# DASH_BOARD_V_2_0.net
KiCad netlist of a schematic drawn in EAGLE
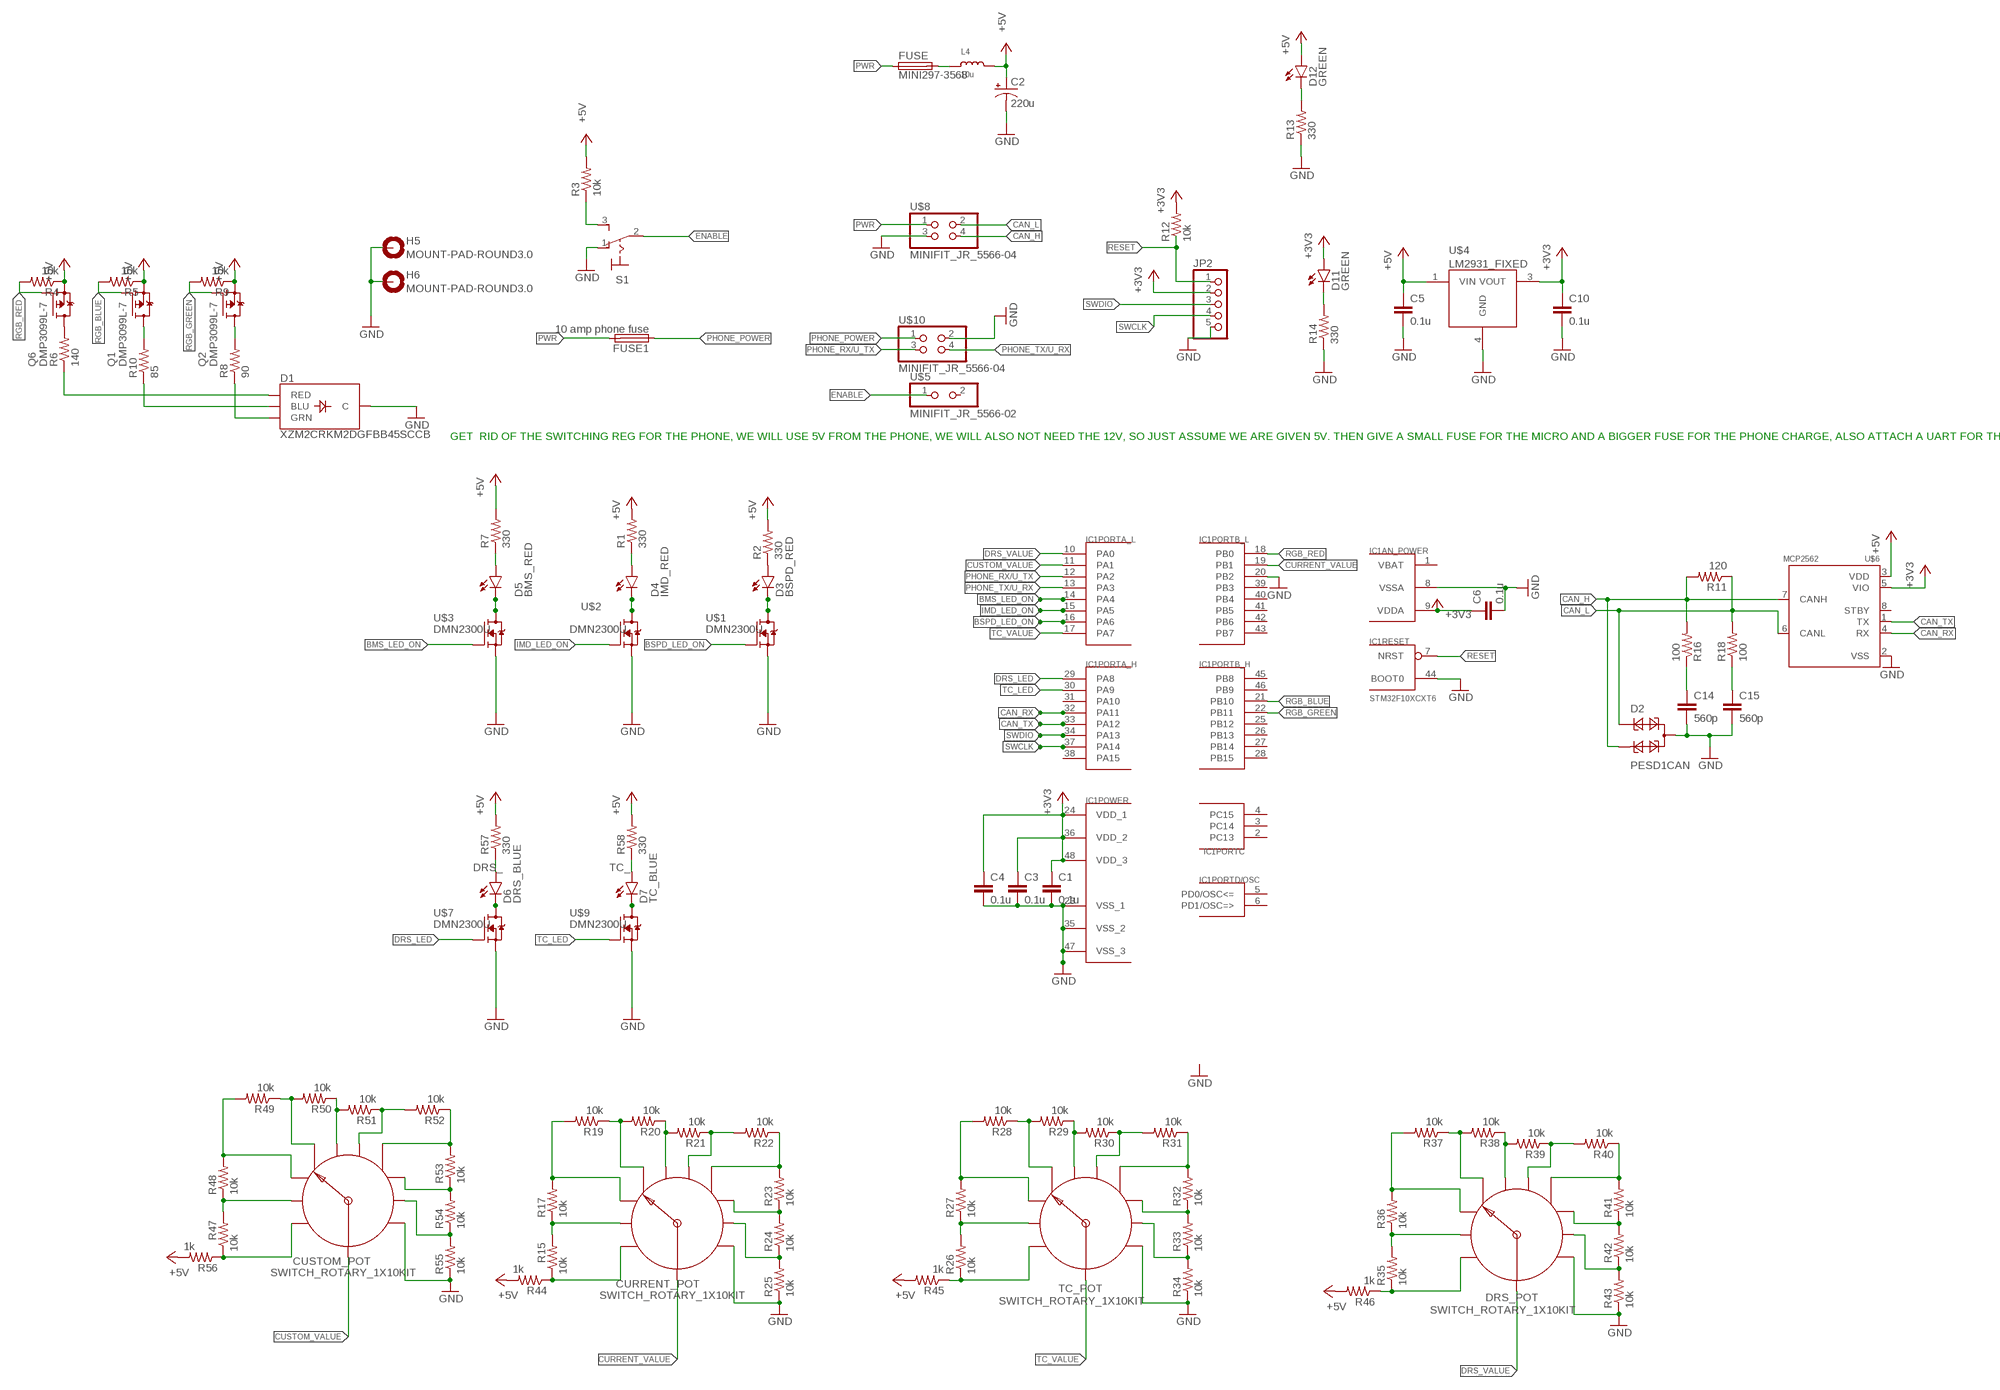
[diagram p0: schematic, sheet 1]

(export (version "E")
  (design (tool "Eeschema 10.0.6"))
  (components
    (comp (ref "C1")
      (value "0.1u")
      (footprint "eagle-import:C0805K")
      (libsource (lib "eagle-import") (part "C-EUC0805K"))
    )
    (comp (ref "C2")
      (value "220u")
      (footprint "eagle-import:E2,5-7")
      (libsource (lib "eagle-import") (part "CPOL-USE2.5-7"))
    )
    (comp (ref "C3")
      (value "0.1u")
      (footprint "eagle-import:C0805K")
      (libsource (lib "eagle-import") (part "C-EUC0805K"))
    )
    (comp (ref "C4")
      (value "0.1u")
      (footprint "eagle-import:C0805K")
      (libsource (lib "eagle-import") (part "C-EUC0805K"))
    )
    (comp (ref "C5")
      (value "0.1u")
      (footprint "eagle-import:C0805K")
      (libsource (lib "eagle-import") (part "C-EUC0805K"))
    )
    (comp (ref "C6")
      (value "0.1u")
      (footprint "eagle-import:C0805K")
      (libsource (lib "eagle-import") (part "C-EUC0805K"))
    )
    (comp (ref "C10")
      (value "0.1u")
      (footprint "eagle-import:C0805K")
      (libsource (lib "eagle-import") (part "C-EUC0805K"))
    )
    (comp (ref "C14")
      (value "560p")
      (footprint "eagle-import:C0805K")
      (libsource (lib "eagle-import") (part "C-EUC0805K"))
    )
    (comp (ref "C15")
      (value "560p")
      (footprint "eagle-import:C0805K")
      (libsource (lib "eagle-import") (part "C-EUC0805K"))
    )
    (comp (ref "CURRENT_POT")
      (value "SWITCH_ROTARY_1X10KIT")
      (footprint "eagle-import:ROTARY_SWITCH_1X10_KIT")
      (libsource (lib "eagle-import") (part "SWITCH_ROTARY_1X10KIT"))
    )
    (comp (ref "CUSTOM_POT")
      (value "SWITCH_ROTARY_1X10KIT")
      (footprint "eagle-import:ROTARY_SWITCH_1X10_KIT")
      (libsource (lib "eagle-import") (part "SWITCH_ROTARY_1X10KIT"))
    )
    (comp (ref "D1")
      (value "XZM2CRKM2DGFBB45SCCB")
      (footprint "eagle-import:PLCC4SMDLED")
      (libsource (lib "eagle-import") (part "SUNLEDSMD1"))
    )
    (comp (ref "D2")
      (value "PESD1CAN")
      (footprint "eagle-import:SOT23")
      (libsource (lib "eagle-import") (part "PESD1CAN"))
    )
    (comp (ref "D3")
      (value "BSPD_RED")
      (footprint "eagle-import:LED-0603")
      (libsource (lib "eagle-import") (part "LED-GREEN0603"))
    )
    (comp (ref "D4")
      (value "IMD_RED")
      (footprint "eagle-import:LED-0603")
      (libsource (lib "eagle-import") (part "LED-GREEN0603"))
    )
    (comp (ref "D5")
      (value "BMS_RED")
      (footprint "eagle-import:LED-0603")
      (libsource (lib "eagle-import") (part "LED-GREEN0603"))
    )
    (comp (ref "D6")
      (value "DRS_BLUE")
      (footprint "eagle-import:LED-0603")
      (libsource (lib "eagle-import") (part "LED-GREEN0603"))
    )
    (comp (ref "D7")
      (value "TC_BLUE")
      (footprint "eagle-import:LED-0603")
      (libsource (lib "eagle-import") (part "LED-GREEN0603"))
    )
    (comp (ref "D11")
      (value "GREEN")
      (footprint "eagle-import:LED-0603")
      (libsource (lib "eagle-import") (part "LED-GREEN0603"))
    )
    (comp (ref "D12")
      (value "GREEN")
      (footprint "eagle-import:LED-0603")
      (libsource (lib "eagle-import") (part "LED-GREEN0603"))
    )
    (comp (ref "DRS_POT")
      (value "SWITCH_ROTARY_1X10KIT")
      (footprint "eagle-import:ROTARY_SWITCH_1X10_KIT")
      (libsource (lib "eagle-import") (part "SWITCH_ROTARY_1X10KIT"))
    )
    (comp (ref "FUSE")
      (value "MINI297-3568")
      (footprint "eagle-import:3568")
      (libsource (lib "eagle-import") (part "MINI297-3568"))
    )
    (comp (ref "FUSE1")
      (value "10 amp phone fuse")
      (footprint "eagle-import:3568")
      (libsource (lib "eagle-import") (part "MINI297-3568"))
    )
    (comp (ref "H5")
      (value "MOUNT-PAD-ROUND3.0")
      (footprint "eagle-import:3,0-PAD")
      (libsource (lib "eagle-import") (part "MOUNT-PAD-ROUND3.0"))
    )
    (comp (ref "H6")
      (value "MOUNT-PAD-ROUND3.0")
      (footprint "eagle-import:3,0-PAD")
      (libsource (lib "eagle-import") (part "MOUNT-PAD-ROUND3.0"))
    )
    (comp (ref "IC1")
      (value "STM32F10XCXT6")
      (footprint "eagle-import:TQFP48")
      (libsource (lib "eagle-import") (part "STM32F10XCXT6"))
    )
    (comp (ref "JP2")
      (value "PINHD-1X5")
      (footprint "eagle-import:1X05")
      (libsource (lib "eagle-import") (part "PINHD-1X5"))
    )
    (comp (ref "L4")
      (value "10u")
      (footprint "eagle-import:INDUCTOR_5X5MM_NR5040_NOTHERMALS")
      (libsource (lib "eagle-import") (part "INDUCTORNR5040"))
    )
    (comp (ref "Q1")
      (value "DMP3099L-7")
      (footprint "eagle-import:SOT23")
      (libsource (lib "eagle-import") (part "DMP3099L-7"))
    )
    (comp (ref "Q2")
      (value "DMP3099L-7")
      (footprint "eagle-import:SOT23")
      (libsource (lib "eagle-import") (part "DMP3099L-7"))
    )
    (comp (ref "Q6")
      (value "DMP3099L-7")
      (footprint "eagle-import:SOT23")
      (libsource (lib "eagle-import") (part "DMP3099L-7"))
    )
    (comp (ref "R1")
      (value "330")
      (footprint "eagle-import:R0805")
      (libsource (lib "eagle-import") (part "resistor_348_R-US_R0805"))
    )
    (comp (ref "R2")
      (value "330")
      (footprint "eagle-import:R0805")
      (libsource (lib "eagle-import") (part "resistor_348_R-US_R0805"))
    )
    (comp (ref "R3")
      (value "10k")
      (footprint "eagle-import:R0805")
      (libsource (lib "eagle-import") (part "resistor_348_R-US_R0805"))
    )
    (comp (ref "R4")
      (value "10k")
      (footprint "eagle-import:R0805")
      (libsource (lib "eagle-import") (part "resistor_348_R-US_R0805"))
    )
    (comp (ref "R5")
      (value "10k")
      (footprint "eagle-import:R0805")
      (libsource (lib "eagle-import") (part "resistor_348_R-US_R0805"))
    )
    (comp (ref "R6")
      (value "140")
      (footprint "eagle-import:R0805")
      (libsource (lib "eagle-import") (part "resistor_348_R-US_R0805"))
    )
    (comp (ref "R7")
      (value "330")
      (footprint "eagle-import:R0805")
      (libsource (lib "eagle-import") (part "resistor_348_R-US_R0805"))
    )
    (comp (ref "R8")
      (value "90")
      (footprint "eagle-import:R0805")
      (libsource (lib "eagle-import") (part "resistor_348_R-US_R0805"))
    )
    (comp (ref "R9")
      (value "10k")
      (footprint "eagle-import:R0805")
      (libsource (lib "eagle-import") (part "resistor_348_R-US_R0805"))
    )
    (comp (ref "R10")
      (value "85")
      (footprint "eagle-import:R0805")
      (libsource (lib "eagle-import") (part "resistor_348_R-US_R0805"))
    )
    (comp (ref "R11")
      (value "120")
      (footprint "eagle-import:R0805")
      (libsource (lib "eagle-import") (part "R-US_R0805"))
    )
    (comp (ref "R12")
      (value "10k")
      (footprint "eagle-import:R0805")
      (libsource (lib "eagle-import") (part "resistor_348_R-US_R0805"))
    )
    (comp (ref "R13")
      (value "330")
      (footprint "eagle-import:R0603")
      (libsource (lib "eagle-import") (part "rcl_334_R-US_R0603"))
    )
    (comp (ref "R14")
      (value "330")
      (footprint "eagle-import:R0603")
      (libsource (lib "eagle-import") (part "rcl_334_R-US_R0603"))
    )
    (comp (ref "R15")
      (value "10k")
      (footprint "eagle-import:R0805")
      (libsource (lib "eagle-import") (part "resistor_348_R-US_R0805"))
    )
    (comp (ref "R16")
      (value "100")
      (footprint "eagle-import:R0805")
      (libsource (lib "eagle-import") (part "R-US_R0805"))
    )
    (comp (ref "R17")
      (value "10k")
      (footprint "eagle-import:R0805")
      (libsource (lib "eagle-import") (part "resistor_348_R-US_R0805"))
    )
    (comp (ref "R18")
      (value "100")
      (footprint "eagle-import:R0805")
      (libsource (lib "eagle-import") (part "R-US_R0805"))
    )
    (comp (ref "R19")
      (value "10k")
      (footprint "eagle-import:R0805")
      (libsource (lib "eagle-import") (part "resistor_348_R-US_R0805"))
    )
    (comp (ref "R20")
      (value "10k")
      (footprint "eagle-import:R0805")
      (libsource (lib "eagle-import") (part "resistor_348_R-US_R0805"))
    )
    (comp (ref "R21")
      (value "10k")
      (footprint "eagle-import:R0805")
      (libsource (lib "eagle-import") (part "resistor_348_R-US_R0805"))
    )
    (comp (ref "R22")
      (value "10k")
      (footprint "eagle-import:R0805")
      (libsource (lib "eagle-import") (part "resistor_348_R-US_R0805"))
    )
    (comp (ref "R23")
      (value "10k")
      (footprint "eagle-import:R0805")
      (libsource (lib "eagle-import") (part "resistor_348_R-US_R0805"))
    )
    (comp (ref "R24")
      (value "10k")
      (footprint "eagle-import:R0805")
      (libsource (lib "eagle-import") (part "resistor_348_R-US_R0805"))
    )
    (comp (ref "R25")
      (value "10k")
      (footprint "eagle-import:R0805")
      (libsource (lib "eagle-import") (part "resistor_348_R-US_R0805"))
    )
    (comp (ref "R26")
      (value "10k")
      (footprint "eagle-import:R0805")
      (libsource (lib "eagle-import") (part "resistor_348_R-US_R0805"))
    )
    (comp (ref "R27")
      (value "10k")
      (footprint "eagle-import:R0805")
      (libsource (lib "eagle-import") (part "resistor_348_R-US_R0805"))
    )
    (comp (ref "R28")
      (value "10k")
      (footprint "eagle-import:R0805")
      (libsource (lib "eagle-import") (part "resistor_348_R-US_R0805"))
    )
    (comp (ref "R29")
      (value "10k")
      (footprint "eagle-import:R0805")
      (libsource (lib "eagle-import") (part "resistor_348_R-US_R0805"))
    )
    (comp (ref "R30")
      (value "10k")
      (footprint "eagle-import:R0805")
      (libsource (lib "eagle-import") (part "resistor_348_R-US_R0805"))
    )
    (comp (ref "R31")
      (value "10k")
      (footprint "eagle-import:R0805")
      (libsource (lib "eagle-import") (part "resistor_348_R-US_R0805"))
    )
    (comp (ref "R32")
      (value "10k")
      (footprint "eagle-import:R0805")
      (libsource (lib "eagle-import") (part "resistor_348_R-US_R0805"))
    )
    (comp (ref "R33")
      (value "10k")
      (footprint "eagle-import:R0805")
      (libsource (lib "eagle-import") (part "resistor_348_R-US_R0805"))
    )
    (comp (ref "R34")
      (value "10k")
      (footprint "eagle-import:R0805")
      (libsource (lib "eagle-import") (part "resistor_348_R-US_R0805"))
    )
    (comp (ref "R35")
      (value "10k")
      (footprint "eagle-import:R0805")
      (libsource (lib "eagle-import") (part "resistor_348_R-US_R0805"))
    )
    (comp (ref "R36")
      (value "10k")
      (footprint "eagle-import:R0805")
      (libsource (lib "eagle-import") (part "resistor_348_R-US_R0805"))
    )
    (comp (ref "R37")
      (value "10k")
      (footprint "eagle-import:R0805")
      (libsource (lib "eagle-import") (part "resistor_348_R-US_R0805"))
    )
    (comp (ref "R38")
      (value "10k")
      (footprint "eagle-import:R0805")
      (libsource (lib "eagle-import") (part "resistor_348_R-US_R0805"))
    )
    (comp (ref "R39")
      (value "10k")
      (footprint "eagle-import:R0805")
      (libsource (lib "eagle-import") (part "resistor_348_R-US_R0805"))
    )
    (comp (ref "R40")
      (value "10k")
      (footprint "eagle-import:R0805")
      (libsource (lib "eagle-import") (part "resistor_348_R-US_R0805"))
    )
    (comp (ref "R41")
      (value "10k")
      (footprint "eagle-import:R0805")
      (libsource (lib "eagle-import") (part "resistor_348_R-US_R0805"))
    )
    (comp (ref "R42")
      (value "10k")
      (footprint "eagle-import:R0805")
      (libsource (lib "eagle-import") (part "resistor_348_R-US_R0805"))
    )
    (comp (ref "R43")
      (value "10k")
      (footprint "eagle-import:R0805")
      (libsource (lib "eagle-import") (part "resistor_348_R-US_R0805"))
    )
    (comp (ref "R44")
      (value "1k")
      (footprint "eagle-import:R0805")
      (libsource (lib "eagle-import") (part "resistor_348_R-US_R0805"))
    )
    (comp (ref "R45")
      (value "1k")
      (footprint "eagle-import:R0805")
      (libsource (lib "eagle-import") (part "resistor_348_R-US_R0805"))
    )
    (comp (ref "R46")
      (value "1k")
      (footprint "eagle-import:R0805")
      (libsource (lib "eagle-import") (part "resistor_348_R-US_R0805"))
    )
    (comp (ref "R47")
      (value "10k")
      (footprint "eagle-import:R0805")
      (libsource (lib "eagle-import") (part "resistor_348_R-US_R0805"))
    )
    (comp (ref "R48")
      (value "10k")
      (footprint "eagle-import:R0805")
      (libsource (lib "eagle-import") (part "resistor_348_R-US_R0805"))
    )
    (comp (ref "R49")
      (value "10k")
      (footprint "eagle-import:R0805")
      (libsource (lib "eagle-import") (part "resistor_348_R-US_R0805"))
    )
    (comp (ref "R50")
      (value "10k")
      (footprint "eagle-import:R0805")
      (libsource (lib "eagle-import") (part "resistor_348_R-US_R0805"))
    )
    (comp (ref "R51")
      (value "10k")
      (footprint "eagle-import:R0805")
      (libsource (lib "eagle-import") (part "resistor_348_R-US_R0805"))
    )
    (comp (ref "R52")
      (value "10k")
      (footprint "eagle-import:R0805")
      (libsource (lib "eagle-import") (part "resistor_348_R-US_R0805"))
    )
    (comp (ref "R53")
      (value "10k")
      (footprint "eagle-import:R0805")
      (libsource (lib "eagle-import") (part "resistor_348_R-US_R0805"))
    )
    (comp (ref "R54")
      (value "10k")
      (footprint "eagle-import:R0805")
      (libsource (lib "eagle-import") (part "resistor_348_R-US_R0805"))
    )
    (comp (ref "R55")
      (value "10k")
      (footprint "eagle-import:R0805")
      (libsource (lib "eagle-import") (part "resistor_348_R-US_R0805"))
    )
    (comp (ref "R56")
      (value "1k")
      (footprint "eagle-import:R0805")
      (libsource (lib "eagle-import") (part "resistor_348_R-US_R0805"))
    )
    (comp (ref "R57")
      (value "330")
      (footprint "eagle-import:R0805")
      (libsource (lib "eagle-import") (part "resistor_348_R-US_R0805"))
    )
    (comp (ref "R58")
      (value "330")
      (footprint "eagle-import:R0805")
      (libsource (lib "eagle-import") (part "resistor_348_R-US_R0805"))
    )
    (comp (ref "S1")
      (value "320-916")
      (footprint "eagle-import:320-916")
      (libsource (lib "eagle-import") (part "320-916"))
    )
    (comp (ref "TC_POT")
      (value "SWITCH_ROTARY_1X10KIT")
      (footprint "eagle-import:ROTARY_SWITCH_1X10_KIT")
      (libsource (lib "eagle-import") (part "SWITCH_ROTARY_1X10KIT"))
    )
    (comp (ref "U$1")
      (value "DMN2300U")
      (footprint "eagle-import:SOT23")
      (libsource (lib "eagle-import") (part "DMN2300U"))
    )
    (comp (ref "U$2")
      (value "DMN2300U")
      (footprint "eagle-import:SOT23")
      (libsource (lib "eagle-import") (part "DMN2300U"))
    )
    (comp (ref "U$3")
      (value "DMN2300U")
      (footprint "eagle-import:SOT23")
      (libsource (lib "eagle-import") (part "DMN2300U"))
    )
    (comp (ref "U$4")
      (value "LM2931_FIXED")
      (footprint "eagle-import:DPAK")
      (libsource (lib "eagle-import") (part "LM2931_FIXED"))
    )
    (comp (ref "U$5")
      (value "MINIFIT_JR_5566-02")
      (footprint "eagle-import:MINIFIT_JR_5566-02")
      (libsource (lib "eagle-import") (part "MINIFIT_JR_5566-02"))
    )
    (comp (ref "U$6")
      (value "MCP2562")
      (footprint "eagle-import:SOIC8")
      (libsource (lib "eagle-import") (part "MCP2562"))
    )
    (comp (ref "U$7")
      (value "DMN2300U")
      (footprint "eagle-import:SOT23")
      (libsource (lib "eagle-import") (part "DMN2300U"))
    )
    (comp (ref "U$8")
      (value "MINIFIT_JR_5566-04")
      (footprint "eagle-import:MINIFIT_JR_5566-04")
      (libsource (lib "eagle-import") (part "MINIFIT_JR_5566-04"))
    )
    (comp (ref "U$9")
      (value "DMN2300U")
      (footprint "eagle-import:SOT23")
      (libsource (lib "eagle-import") (part "DMN2300U"))
    )
    (comp (ref "U$10")
      (value "MINIFIT_JR_5566-04")
      (footprint "eagle-import:MINIFIT_JR_5566-04")
      (libsource (lib "eagle-import") (part "MINIFIT_JR_5566-04"))
    )
  )
  (nets
    (net (code "1") (name "+3V3") (class "Default")
      (node (ref "C1") (pin "1") (pinfunction "1_1") (pintype "passive"))
      (node (ref "C10") (pin "1") (pinfunction "1_1") (pintype "passive"))
      (node (ref "C3") (pin "1") (pinfunction "1_1") (pintype "passive"))
      (node (ref "C4") (pin "1") (pinfunction "1_1") (pintype "passive"))
      (node (ref "C6") (pin "1") (pinfunction "1_1") (pintype "passive"))
      (node (ref "D11") (pin "A") (pinfunction "A_A") (pintype "passive"))
      (node (ref "IC1") (pin "24") (pinfunction "VDD_1_24") (pintype "power_in"))
      (node (ref "IC1") (pin "36") (pinfunction "VDD_2_36") (pintype "power_in"))
      (node (ref "IC1") (pin "48") (pinfunction "VDD_3_48") (pintype "power_in"))
      (node (ref "IC1") (pin "9") (pinfunction "VDDA_9") (pintype "power_in"))
      (node (ref "JP2") (pin "2") (pinfunction "2_2") (pintype "passive"))
      (node (ref "R12") (pin "2") (pinfunction "2_2") (pintype "passive"))
      (node (ref "U$4") (pin "3") (pinfunction "VOUT_3") (pintype "bidirectional"))
      (node (ref "U$6") (pin "5") (pinfunction "VIO_5") (pintype "bidirectional"))
    )
    (net (code "2") (name "+5V") (class "Default")
      (node (ref "C2") (pin "+") (pinfunction "+_+") (pintype "passive"))
      (node (ref "C5") (pin "1") (pinfunction "1_1") (pintype "passive"))
      (node (ref "D12") (pin "A") (pinfunction "A_A") (pintype "passive"))
      (node (ref "L4") (pin "P$2") (pinfunction "2_P$2") (pintype "passive"))
      (node (ref "Q1") (pin "2") (pinfunction "S_2") (pintype "passive"))
      (node (ref "Q2") (pin "2") (pinfunction "S_2") (pintype "passive"))
      (node (ref "Q6") (pin "2") (pinfunction "S_2") (pintype "passive"))
      (node (ref "R1") (pin "2") (pinfunction "2_2") (pintype "passive"))
      (node (ref "R2") (pin "2") (pinfunction "2_2") (pintype "passive"))
      (node (ref "R3") (pin "2") (pinfunction "2_2") (pintype "passive"))
      (node (ref "R4") (pin "1") (pinfunction "1_1") (pintype "passive"))
      (node (ref "R44") (pin "2") (pinfunction "2_2") (pintype "passive"))
      (node (ref "R45") (pin "2") (pinfunction "2_2") (pintype "passive"))
      (node (ref "R46") (pin "2") (pinfunction "2_2") (pintype "passive"))
      (node (ref "R5") (pin "1") (pinfunction "1_1") (pintype "passive"))
      (node (ref "R56") (pin "2") (pinfunction "2_2") (pintype "passive"))
      (node (ref "R57") (pin "2") (pinfunction "2_2") (pintype "passive"))
      (node (ref "R58") (pin "2") (pinfunction "2_2") (pintype "passive"))
      (node (ref "R7") (pin "2") (pinfunction "2_2") (pintype "passive"))
      (node (ref "R9") (pin "1") (pinfunction "1_1") (pintype "passive"))
      (node (ref "U$4") (pin "1") (pinfunction "VIN_1") (pintype "bidirectional"))
      (node (ref "U$6") (pin "3") (pinfunction "VDD_3") (pintype "bidirectional"))
    )
    (net (code "3") (name "/DRS_") (class "Default")
      (node (ref "D6") (pin "A") (pinfunction "A_A") (pintype "passive"))
      (node (ref "R57") (pin "1") (pinfunction "1_1") (pintype "passive"))
    )
    (net (code "4") (name "/TC_") (class "Default")
      (node (ref "D7") (pin "A") (pinfunction "A_A") (pintype "passive"))
      (node (ref "R58") (pin "1") (pinfunction "1_1") (pintype "passive"))
    )
    (net (code "5") (name "/VBAT") (class "Default")
      (node (ref "IC1") (pin "1") (pinfunction "VBAT_1") (pintype "power_in"))
    )
    (net (code "6") (name "BMS_LED_ON") (class "Default")
      (node (ref "IC1") (pin "14") (pinfunction "PA4_14") (pintype "bidirectional"))
      (node (ref "U$3") (pin "1") (pinfunction "G_1") (pintype "passive"))
    )
    (net (code "7") (name "BSPD_LED_ON") (class "Default")
      (node (ref "IC1") (pin "16") (pinfunction "PA6_16") (pintype "bidirectional"))
      (node (ref "U$1") (pin "1") (pinfunction "G_1") (pintype "passive"))
    )
    (net (code "8") (name "CAN_H") (class "Default")
      (node (ref "D2") (pin "2") (pinfunction "2_2") (pintype "passive"))
      (node (ref "R11") (pin "2") (pinfunction "2_2") (pintype "passive"))
      (node (ref "R16") (pin "2") (pinfunction "2_2") (pintype "passive"))
      (node (ref "U$6") (pin "7") (pinfunction "CANH_7") (pintype "bidirectional"))
      (node (ref "U$8") (pin "4") (pinfunction "4_4") (pintype "passive"))
    )
    (net (code "9") (name "CAN_L") (class "Default")
      (node (ref "D2") (pin "1") (pinfunction "1_1") (pintype "passive"))
      (node (ref "R11") (pin "1") (pinfunction "1_1") (pintype "passive"))
      (node (ref "R18") (pin "2") (pinfunction "2_2") (pintype "passive"))
      (node (ref "U$6") (pin "6") (pinfunction "CANL_6") (pintype "bidirectional"))
      (node (ref "U$8") (pin "2") (pinfunction "2_2") (pintype "passive"))
    )
    (net (code "10") (name "CAN_RX") (class "Default")
      (node (ref "IC1") (pin "32") (pinfunction "PA11_32") (pintype "bidirectional"))
      (node (ref "U$6") (pin "4") (pinfunction "RX_4") (pintype "bidirectional"))
    )
    (net (code "11") (name "CAN_TX") (class "Default")
      (node (ref "IC1") (pin "33") (pinfunction "PA12_33") (pintype "bidirectional"))
      (node (ref "U$6") (pin "1") (pinfunction "TX_1") (pintype "bidirectional"))
    )
    (net (code "12") (name "CURRENT_VALUE") (class "Default")
      (node (ref "CURRENT_POT") (pin "COMMON") (pinfunction "COMMON_COMMON") (pintype "bidirectional"))
      (node (ref "IC1") (pin "19") (pinfunction "PB1_19") (pintype "bidirectional"))
    )
    (net (code "13") (name "CUSTOM_VALUE") (class "Default")
      (node (ref "CUSTOM_POT") (pin "COMMON") (pinfunction "COMMON_COMMON") (pintype "bidirectional"))
      (node (ref "IC1") (pin "11") (pinfunction "PA1_11") (pintype "bidirectional"))
    )
    (net (code "14") (name "DRS_LED") (class "Default")
      (node (ref "IC1") (pin "29") (pinfunction "PA8_29") (pintype "bidirectional"))
      (node (ref "U$7") (pin "1") (pinfunction "G_1") (pintype "passive"))
    )
    (net (code "15") (name "DRS_VALUE") (class "Default")
      (node (ref "DRS_POT") (pin "COMMON") (pinfunction "COMMON_COMMON") (pintype "bidirectional"))
      (node (ref "IC1") (pin "10") (pinfunction "PA0_10") (pintype "bidirectional"))
    )
    (net (code "16") (name "ENABLE") (class "Default")
      (node (ref "S1") (pin "2") (pinfunction "P_2") (pintype "passive"))
      (node (ref "U$5") (pin "1") (pinfunction "1_1") (pintype "passive"))
    )
    (net (code "17") (name "GND") (class "Default")
      (node (ref "C1") (pin "2") (pinfunction "2_2") (pintype "passive"))
      (node (ref "C10") (pin "2") (pinfunction "2_2") (pintype "passive"))
      (node (ref "C14") (pin "2") (pinfunction "2_2") (pintype "passive"))
      (node (ref "C15") (pin "2") (pinfunction "2_2") (pintype "passive"))
      (node (ref "C2") (pin "-") (pinfunction "-_-") (pintype "passive"))
      (node (ref "C3") (pin "2") (pinfunction "2_2") (pintype "passive"))
      (node (ref "C4") (pin "2") (pinfunction "2_2") (pintype "passive"))
      (node (ref "C5") (pin "2") (pinfunction "2_2") (pintype "passive"))
      (node (ref "C6") (pin "2") (pinfunction "2_2") (pintype "passive"))
      (node (ref "CURRENT_POT") (pin "10") (pinfunction "10_10") (pintype "bidirectional"))
      (node (ref "CUSTOM_POT") (pin "10") (pinfunction "10_10") (pintype "bidirectional"))
      (node (ref "D1") (pin "4") (pinfunction "C_4") (pintype "bidirectional"))
      (node (ref "D2") (pin "3") (pinfunction "3_3") (pintype "passive"))
      (node (ref "DRS_POT") (pin "10") (pinfunction "10_10") (pintype "bidirectional"))
      (node (ref "H5") (pin "B3,0") (pinfunction "MOUNT_B3,0") (pintype "passive"))
      (node (ref "H6") (pin "B3,0") (pinfunction "MOUNT_B3,0") (pintype "passive"))
      (node (ref "IC1") (pin "20") (pinfunction "PB2_20") (pintype "bidirectional"))
      (node (ref "IC1") (pin "23") (pinfunction "VSS_1_23") (pintype "power_in"))
      (node (ref "IC1") (pin "35") (pinfunction "VSS_2_35") (pintype "power_in"))
      (node (ref "IC1") (pin "44") (pinfunction "BOOT0_44") (pintype "input"))
      (node (ref "IC1") (pin "47") (pinfunction "VSS_3_47") (pintype "power_in"))
      (node (ref "IC1") (pin "8") (pinfunction "VSSA_8") (pintype "power_in"))
      (node (ref "JP2") (pin "5") (pinfunction "5_5") (pintype "passive"))
      (node (ref "R13") (pin "1") (pinfunction "1_1") (pintype "passive"))
      (node (ref "R14") (pin "1") (pinfunction "1_1") (pintype "passive"))
      (node (ref "R25") (pin "1") (pinfunction "1_1") (pintype "passive"))
      (node (ref "R34") (pin "1") (pinfunction "1_1") (pintype "passive"))
      (node (ref "R43") (pin "1") (pinfunction "1_1") (pintype "passive"))
      (node (ref "R55") (pin "1") (pinfunction "1_1") (pintype "passive"))
      (node (ref "S1") (pin "1") (pinfunction "O_1") (pintype "passive"))
      (node (ref "TC_POT") (pin "10") (pinfunction "10_10") (pintype "bidirectional"))
      (node (ref "U$1") (pin "2") (pinfunction "S_2") (pintype "passive"))
      (node (ref "U$10") (pin "2") (pinfunction "2_2") (pintype "passive"))
      (node (ref "U$2") (pin "2") (pinfunction "S_2") (pintype "passive"))
      (node (ref "U$3") (pin "2") (pinfunction "S_2") (pintype "passive"))
      (node (ref "U$4") (pin "4") (pinfunction "GND_4") (pintype "bidirectional"))
      (node (ref "U$6") (pin "2") (pinfunction "VSS_2") (pintype "bidirectional"))
      (node (ref "U$7") (pin "2") (pinfunction "S_2") (pintype "passive"))
      (node (ref "U$8") (pin "3") (pinfunction "3_3") (pintype "passive"))
      (node (ref "U$9") (pin "2") (pinfunction "S_2") (pintype "passive"))
    )
    (net (code "18") (name "IMD_LED_ON") (class "Default")
      (node (ref "IC1") (pin "15") (pinfunction "PA5_15") (pintype "bidirectional"))
      (node (ref "U$2") (pin "1") (pinfunction "G_1") (pintype "passive"))
    )
    (net (code "19") (name "Net-(C14-Pad1)") (class "Default")
      (node (ref "C14") (pin "1") (pinfunction "1_1") (pintype "passive"))
      (node (ref "R16") (pin "1") (pinfunction "1_1") (pintype "passive"))
    )
    (net (code "20") (name "Net-(C15-Pad1)") (class "Default")
      (node (ref "C15") (pin "1") (pinfunction "1_1") (pintype "passive"))
      (node (ref "R18") (pin "1") (pinfunction "1_1") (pintype "passive"))
    )
    (net (code "21") (name "Net-(CURRENT_POT-Pad1)") (class "Default")
      (node (ref "CURRENT_POT") (pin "1") (pinfunction "1_1") (pintype "bidirectional"))
      (node (ref "R15") (pin "1") (pinfunction "1_1") (pintype "passive"))
      (node (ref "R44") (pin "1") (pinfunction "1_1") (pintype "passive"))
    )
    (net (code "22") (name "Net-(CURRENT_POT-Pad2)") (class "Default")
      (node (ref "CURRENT_POT") (pin "2") (pinfunction "2_2") (pintype "bidirectional"))
      (node (ref "R15") (pin "2") (pinfunction "2_2") (pintype "passive"))
      (node (ref "R17") (pin "1") (pinfunction "1_1") (pintype "passive"))
    )
    (net (code "23") (name "Net-(CURRENT_POT-Pad3)") (class "Default")
      (node (ref "CURRENT_POT") (pin "3") (pinfunction "3_3") (pintype "bidirectional"))
      (node (ref "R17") (pin "2") (pinfunction "2_2") (pintype "passive"))
      (node (ref "R19") (pin "2") (pinfunction "2_2") (pintype "passive"))
    )
    (net (code "24") (name "Net-(CURRENT_POT-Pad4)") (class "Default")
      (node (ref "CURRENT_POT") (pin "4") (pinfunction "4_4") (pintype "bidirectional"))
      (node (ref "R19") (pin "1") (pinfunction "1_1") (pintype "passive"))
      (node (ref "R20") (pin "2") (pinfunction "2_2") (pintype "passive"))
    )
    (net (code "25") (name "Net-(CURRENT_POT-Pad5)") (class "Default")
      (node (ref "CURRENT_POT") (pin "5") (pinfunction "5_5") (pintype "bidirectional"))
      (node (ref "R20") (pin "1") (pinfunction "1_1") (pintype "passive"))
      (node (ref "R21") (pin "2") (pinfunction "2_2") (pintype "passive"))
    )
    (net (code "26") (name "Net-(CURRENT_POT-Pad6)") (class "Default")
      (node (ref "CURRENT_POT") (pin "6") (pinfunction "6_6") (pintype "bidirectional"))
      (node (ref "R21") (pin "1") (pinfunction "1_1") (pintype "passive"))
      (node (ref "R22") (pin "2") (pinfunction "2_2") (pintype "passive"))
    )
    (net (code "27") (name "Net-(CURRENT_POT-Pad7)") (class "Default")
      (node (ref "CURRENT_POT") (pin "7") (pinfunction "7_7") (pintype "bidirectional"))
      (node (ref "R22") (pin "1") (pinfunction "1_1") (pintype "passive"))
      (node (ref "R23") (pin "2") (pinfunction "2_2") (pintype "passive"))
    )
    (net (code "28") (name "Net-(CURRENT_POT-Pad8)") (class "Default")
      (node (ref "CURRENT_POT") (pin "8") (pinfunction "8_8") (pintype "bidirectional"))
      (node (ref "R23") (pin "1") (pinfunction "1_1") (pintype "passive"))
      (node (ref "R24") (pin "2") (pinfunction "2_2") (pintype "passive"))
    )
    (net (code "29") (name "Net-(CURRENT_POT-Pad9)") (class "Default")
      (node (ref "CURRENT_POT") (pin "9") (pinfunction "9_9") (pintype "bidirectional"))
      (node (ref "R24") (pin "1") (pinfunction "1_1") (pintype "passive"))
      (node (ref "R25") (pin "2") (pinfunction "2_2") (pintype "passive"))
    )
    (net (code "30") (name "Net-(CUSTOM_POT-Pad1)") (class "Default")
      (node (ref "CUSTOM_POT") (pin "1") (pinfunction "1_1") (pintype "bidirectional"))
      (node (ref "R47") (pin "1") (pinfunction "1_1") (pintype "passive"))
      (node (ref "R56") (pin "1") (pinfunction "1_1") (pintype "passive"))
    )
    (net (code "31") (name "Net-(CUSTOM_POT-Pad2)") (class "Default")
      (node (ref "CUSTOM_POT") (pin "2") (pinfunction "2_2") (pintype "bidirectional"))
      (node (ref "R47") (pin "2") (pinfunction "2_2") (pintype "passive"))
      (node (ref "R48") (pin "1") (pinfunction "1_1") (pintype "passive"))
    )
    (net (code "32") (name "Net-(CUSTOM_POT-Pad3)") (class "Default")
      (node (ref "CUSTOM_POT") (pin "3") (pinfunction "3_3") (pintype "bidirectional"))
      (node (ref "R48") (pin "2") (pinfunction "2_2") (pintype "passive"))
      (node (ref "R49") (pin "2") (pinfunction "2_2") (pintype "passive"))
    )
    (net (code "33") (name "Net-(CUSTOM_POT-Pad4)") (class "Default")
      (node (ref "CUSTOM_POT") (pin "4") (pinfunction "4_4") (pintype "bidirectional"))
      (node (ref "R49") (pin "1") (pinfunction "1_1") (pintype "passive"))
      (node (ref "R50") (pin "2") (pinfunction "2_2") (pintype "passive"))
    )
    (net (code "34") (name "Net-(CUSTOM_POT-Pad5)") (class "Default")
      (node (ref "CUSTOM_POT") (pin "5") (pinfunction "5_5") (pintype "bidirectional"))
      (node (ref "R50") (pin "1") (pinfunction "1_1") (pintype "passive"))
      (node (ref "R51") (pin "2") (pinfunction "2_2") (pintype "passive"))
    )
    (net (code "35") (name "Net-(CUSTOM_POT-Pad6)") (class "Default")
      (node (ref "CUSTOM_POT") (pin "6") (pinfunction "6_6") (pintype "bidirectional"))
      (node (ref "R51") (pin "1") (pinfunction "1_1") (pintype "passive"))
      (node (ref "R52") (pin "2") (pinfunction "2_2") (pintype "passive"))
    )
    (net (code "36") (name "Net-(CUSTOM_POT-Pad7)") (class "Default")
      (node (ref "CUSTOM_POT") (pin "7") (pinfunction "7_7") (pintype "bidirectional"))
      (node (ref "R52") (pin "1") (pinfunction "1_1") (pintype "passive"))
      (node (ref "R53") (pin "2") (pinfunction "2_2") (pintype "passive"))
    )
    (net (code "37") (name "Net-(CUSTOM_POT-Pad8)") (class "Default")
      (node (ref "CUSTOM_POT") (pin "8") (pinfunction "8_8") (pintype "bidirectional"))
      (node (ref "R53") (pin "1") (pinfunction "1_1") (pintype "passive"))
      (node (ref "R54") (pin "2") (pinfunction "2_2") (pintype "passive"))
    )
    (net (code "38") (name "Net-(CUSTOM_POT-Pad9)") (class "Default")
      (node (ref "CUSTOM_POT") (pin "9") (pinfunction "9_9") (pintype "bidirectional"))
      (node (ref "R54") (pin "1") (pinfunction "1_1") (pintype "passive"))
      (node (ref "R55") (pin "2") (pinfunction "2_2") (pintype "passive"))
    )
    (net (code "39") (name "Net-(D1-BLU)") (class "Default")
      (node (ref "D1") (pin "3") (pinfunction "BLU_3") (pintype "bidirectional"))
      (node (ref "R10") (pin "1") (pinfunction "1_1") (pintype "passive"))
    )
    (net (code "40") (name "Net-(D1-GRN)") (class "Default")
      (node (ref "D1") (pin "2") (pinfunction "GRN_2") (pintype "bidirectional"))
      (node (ref "R8") (pin "1") (pinfunction "1_1") (pintype "passive"))
    )
    (net (code "41") (name "Net-(D1-RED)") (class "Default")
      (node (ref "D1") (pin "1") (pinfunction "RED_1") (pintype "bidirectional"))
      (node (ref "R6") (pin "1") (pinfunction "1_1") (pintype "passive"))
    )
    (net (code "42") (name "Net-(D3-PadA)") (class "Default")
      (node (ref "D3") (pin "A") (pinfunction "A_A") (pintype "passive"))
      (node (ref "R2") (pin "1") (pinfunction "1_1") (pintype "passive"))
    )
    (net (code "43") (name "Net-(D4-PadA)") (class "Default")
      (node (ref "D4") (pin "A") (pinfunction "A_A") (pintype "passive"))
      (node (ref "R1") (pin "1") (pinfunction "1_1") (pintype "passive"))
    )
    (net (code "44") (name "Net-(D5-PadA)") (class "Default")
      (node (ref "D5") (pin "A") (pinfunction "A_A") (pintype "passive"))
      (node (ref "R7") (pin "1") (pinfunction "1_1") (pintype "passive"))
    )
    (net (code "45") (name "Net-(D11-PadC)") (class "Default")
      (node (ref "D11") (pin "C") (pinfunction "C_C") (pintype "passive"))
      (node (ref "R14") (pin "2") (pinfunction "2_2") (pintype "passive"))
    )
    (net (code "46") (name "Net-(D12-PadC)") (class "Default")
      (node (ref "D12") (pin "C") (pinfunction "C_C") (pintype "passive"))
      (node (ref "R13") (pin "2") (pinfunction "2_2") (pintype "passive"))
    )
    (net (code "47") (name "Net-(DRS_POT-Pad1)") (class "Default")
      (node (ref "DRS_POT") (pin "1") (pinfunction "1_1") (pintype "bidirectional"))
      (node (ref "R35") (pin "1") (pinfunction "1_1") (pintype "passive"))
      (node (ref "R46") (pin "1") (pinfunction "1_1") (pintype "passive"))
    )
    (net (code "48") (name "Net-(DRS_POT-Pad2)") (class "Default")
      (node (ref "DRS_POT") (pin "2") (pinfunction "2_2") (pintype "bidirectional"))
      (node (ref "R35") (pin "2") (pinfunction "2_2") (pintype "passive"))
      (node (ref "R36") (pin "1") (pinfunction "1_1") (pintype "passive"))
    )
    (net (code "49") (name "Net-(DRS_POT-Pad3)") (class "Default")
      (node (ref "DRS_POT") (pin "3") (pinfunction "3_3") (pintype "bidirectional"))
      (node (ref "R36") (pin "2") (pinfunction "2_2") (pintype "passive"))
      (node (ref "R37") (pin "2") (pinfunction "2_2") (pintype "passive"))
    )
    (net (code "50") (name "Net-(DRS_POT-Pad4)") (class "Default")
      (node (ref "DRS_POT") (pin "4") (pinfunction "4_4") (pintype "bidirectional"))
      (node (ref "R37") (pin "1") (pinfunction "1_1") (pintype "passive"))
      (node (ref "R38") (pin "2") (pinfunction "2_2") (pintype "passive"))
    )
    (net (code "51") (name "Net-(DRS_POT-Pad5)") (class "Default")
      (node (ref "DRS_POT") (pin "5") (pinfunction "5_5") (pintype "bidirectional"))
      (node (ref "R38") (pin "1") (pinfunction "1_1") (pintype "passive"))
      (node (ref "R39") (pin "2") (pinfunction "2_2") (pintype "passive"))
    )
    (net (code "52") (name "Net-(DRS_POT-Pad6)") (class "Default")
      (node (ref "DRS_POT") (pin "6") (pinfunction "6_6") (pintype "bidirectional"))
      (node (ref "R39") (pin "1") (pinfunction "1_1") (pintype "passive"))
      (node (ref "R40") (pin "2") (pinfunction "2_2") (pintype "passive"))
    )
    (net (code "53") (name "Net-(DRS_POT-Pad7)") (class "Default")
      (node (ref "DRS_POT") (pin "7") (pinfunction "7_7") (pintype "bidirectional"))
      (node (ref "R40") (pin "1") (pinfunction "1_1") (pintype "passive"))
      (node (ref "R41") (pin "2") (pinfunction "2_2") (pintype "passive"))
    )
    (net (code "54") (name "Net-(DRS_POT-Pad8)") (class "Default")
      (node (ref "DRS_POT") (pin "8") (pinfunction "8_8") (pintype "bidirectional"))
      (node (ref "R41") (pin "1") (pinfunction "1_1") (pintype "passive"))
      (node (ref "R42") (pin "2") (pinfunction "2_2") (pintype "passive"))
    )
    (net (code "55") (name "Net-(DRS_POT-Pad9)") (class "Default")
      (node (ref "DRS_POT") (pin "9") (pinfunction "9_9") (pintype "bidirectional"))
      (node (ref "R42") (pin "1") (pinfunction "1_1") (pintype "passive"))
      (node (ref "R43") (pin "2") (pinfunction "2_2") (pintype "passive"))
    )
    (net (code "56") (name "Net-(L4-1)") (class "Default")
      (node (ref "FUSE") (pin "P$2") (pinfunction "2_P$2") (pintype "passive"))
      (node (ref "FUSE") (pin "P$3") (pinfunction "2_P$3") (pintype "passive"))
      (node (ref "L4") (pin "P$1") (pinfunction "1_P$1") (pintype "passive"))
    )
    (net (code "57") (name "Net-(Q1-D)") (class "Default")
      (node (ref "Q1") (pin "3") (pinfunction "D_3") (pintype "passive"))
      (node (ref "R10") (pin "2") (pinfunction "2_2") (pintype "passive"))
    )
    (net (code "58") (name "Net-(Q2-D)") (class "Default")
      (node (ref "Q2") (pin "3") (pinfunction "D_3") (pintype "passive"))
      (node (ref "R8") (pin "2") (pinfunction "2_2") (pintype "passive"))
    )
    (net (code "59") (name "Net-(Q6-D)") (class "Default")
      (node (ref "Q6") (pin "3") (pinfunction "D_3") (pintype "passive"))
      (node (ref "R6") (pin "2") (pinfunction "2_2") (pintype "passive"))
    )
    (net (code "60") (name "Net-(R26-Pad1)") (class "Default")
      (node (ref "R26") (pin "1") (pinfunction "1_1") (pintype "passive"))
      (node (ref "R45") (pin "1") (pinfunction "1_1") (pintype "passive"))
      (node (ref "TC_POT") (pin "1") (pinfunction "1_1") (pintype "bidirectional"))
    )
    (net (code "61") (name "Net-(R26-Pad2)") (class "Default")
      (node (ref "R26") (pin "2") (pinfunction "2_2") (pintype "passive"))
      (node (ref "R27") (pin "1") (pinfunction "1_1") (pintype "passive"))
      (node (ref "TC_POT") (pin "2") (pinfunction "2_2") (pintype "bidirectional"))
    )
    (net (code "62") (name "Net-(R27-Pad2)") (class "Default")
      (node (ref "R27") (pin "2") (pinfunction "2_2") (pintype "passive"))
      (node (ref "R28") (pin "2") (pinfunction "2_2") (pintype "passive"))
      (node (ref "TC_POT") (pin "3") (pinfunction "3_3") (pintype "bidirectional"))
    )
    (net (code "63") (name "Net-(R28-Pad1)") (class "Default")
      (node (ref "R28") (pin "1") (pinfunction "1_1") (pintype "passive"))
      (node (ref "R29") (pin "2") (pinfunction "2_2") (pintype "passive"))
      (node (ref "TC_POT") (pin "4") (pinfunction "4_4") (pintype "bidirectional"))
    )
    (net (code "64") (name "Net-(R29-Pad1)") (class "Default")
      (node (ref "R29") (pin "1") (pinfunction "1_1") (pintype "passive"))
      (node (ref "R30") (pin "2") (pinfunction "2_2") (pintype "passive"))
      (node (ref "TC_POT") (pin "5") (pinfunction "5_5") (pintype "bidirectional"))
    )
    (net (code "65") (name "Net-(R30-Pad1)") (class "Default")
      (node (ref "R30") (pin "1") (pinfunction "1_1") (pintype "passive"))
      (node (ref "R31") (pin "2") (pinfunction "2_2") (pintype "passive"))
      (node (ref "TC_POT") (pin "6") (pinfunction "6_6") (pintype "bidirectional"))
    )
    (net (code "66") (name "Net-(R31-Pad1)") (class "Default")
      (node (ref "R31") (pin "1") (pinfunction "1_1") (pintype "passive"))
      (node (ref "R32") (pin "2") (pinfunction "2_2") (pintype "passive"))
      (node (ref "TC_POT") (pin "7") (pinfunction "7_7") (pintype "bidirectional"))
    )
    (net (code "67") (name "Net-(R32-Pad1)") (class "Default")
      (node (ref "R32") (pin "1") (pinfunction "1_1") (pintype "passive"))
      (node (ref "R33") (pin "2") (pinfunction "2_2") (pintype "passive"))
      (node (ref "TC_POT") (pin "8") (pinfunction "8_8") (pintype "bidirectional"))
    )
    (net (code "68") (name "Net-(R33-Pad1)") (class "Default")
      (node (ref "R33") (pin "1") (pinfunction "1_1") (pintype "passive"))
      (node (ref "R34") (pin "2") (pinfunction "2_2") (pintype "passive"))
      (node (ref "TC_POT") (pin "9") (pinfunction "9_9") (pintype "bidirectional"))
    )
    (net (code "69") (name "Net-(S1-S)") (class "Default")
      (node (ref "R3") (pin "1") (pinfunction "1_1") (pintype "passive"))
      (node (ref "S1") (pin "3") (pinfunction "S_3") (pintype "passive"))
    )
    (net (code "70") (name "Net-(U$1-D)") (class "Default")
      (node (ref "D3") (pin "C") (pinfunction "C_C") (pintype "passive"))
      (node (ref "U$1") (pin "3") (pinfunction "D_3") (pintype "passive"))
    )
    (net (code "71") (name "Net-(U$2-D)") (class "Default")
      (node (ref "D4") (pin "C") (pinfunction "C_C") (pintype "passive"))
      (node (ref "U$2") (pin "3") (pinfunction "D_3") (pintype "passive"))
    )
    (net (code "72") (name "Net-(U$3-D)") (class "Default")
      (node (ref "D5") (pin "C") (pinfunction "C_C") (pintype "passive"))
      (node (ref "U$3") (pin "3") (pinfunction "D_3") (pintype "passive"))
    )
    (net (code "73") (name "Net-(U$7-D)") (class "Default")
      (node (ref "D6") (pin "C") (pinfunction "C_C") (pintype "passive"))
      (node (ref "U$7") (pin "3") (pinfunction "D_3") (pintype "passive"))
    )
    (net (code "74") (name "Net-(U$9-D)") (class "Default")
      (node (ref "D7") (pin "C") (pinfunction "C_C") (pintype "passive"))
      (node (ref "U$9") (pin "3") (pinfunction "D_3") (pintype "passive"))
    )
    (net (code "75") (name "PHONE_POWER") (class "Default")
      (node (ref "FUSE1") (pin "P$1") (pinfunction "1_P$1") (pintype "passive"))
      (node (ref "FUSE1") (pin "P$4") (pinfunction "1_P$4") (pintype "passive"))
      (node (ref "U$10") (pin "1") (pinfunction "1_1") (pintype "passive"))
    )
    (net (code "76") (name "PHONE_RX{slash}U_TX") (class "Default")
      (node (ref "IC1") (pin "12") (pinfunction "PA2_12") (pintype "bidirectional"))
      (node (ref "U$10") (pin "3") (pinfunction "3_3") (pintype "passive"))
    )
    (net (code "77") (name "PHONE_TX{slash}U_RX") (class "Default")
      (node (ref "IC1") (pin "13") (pinfunction "PA3_13") (pintype "bidirectional"))
      (node (ref "U$10") (pin "4") (pinfunction "4_4") (pintype "passive"))
    )
    (net (code "78") (name "PWR") (class "Default")
      (node (ref "FUSE") (pin "P$1") (pinfunction "1_P$1") (pintype "passive"))
      (node (ref "FUSE") (pin "P$4") (pinfunction "1_P$4") (pintype "passive"))
      (node (ref "FUSE1") (pin "P$2") (pinfunction "2_P$2") (pintype "passive"))
      (node (ref "FUSE1") (pin "P$3") (pinfunction "2_P$3") (pintype "passive"))
      (node (ref "U$8") (pin "1") (pinfunction "1_1") (pintype "passive"))
    )
    (net (code "79") (name "RESET") (class "Default")
      (node (ref "IC1") (pin "7") (pinfunction "NRST_7") (pintype "input"))
      (node (ref "JP2") (pin "1") (pinfunction "1_1") (pintype "passive"))
      (node (ref "R12") (pin "1") (pinfunction "1_1") (pintype "passive"))
    )
    (net (code "80") (name "RGB_BLUE") (class "Default")
      (node (ref "IC1") (pin "21") (pinfunction "PB10_21") (pintype "bidirectional"))
      (node (ref "Q1") (pin "1") (pinfunction "G_1") (pintype "passive"))
      (node (ref "R5") (pin "2") (pinfunction "2_2") (pintype "passive"))
    )
    (net (code "81") (name "RGB_GREEN") (class "Default")
      (node (ref "IC1") (pin "22") (pinfunction "PB11_22") (pintype "bidirectional"))
      (node (ref "Q2") (pin "1") (pinfunction "G_1") (pintype "passive"))
      (node (ref "R9") (pin "2") (pinfunction "2_2") (pintype "passive"))
    )
    (net (code "82") (name "RGB_RED") (class "Default")
      (node (ref "IC1") (pin "18") (pinfunction "PB0_18") (pintype "bidirectional"))
      (node (ref "Q6") (pin "1") (pinfunction "G_1") (pintype "passive"))
      (node (ref "R4") (pin "2") (pinfunction "2_2") (pintype "passive"))
    )
    (net (code "83") (name "SWCLK") (class "Default")
      (node (ref "IC1") (pin "37") (pinfunction "PA14_37") (pintype "bidirectional"))
      (node (ref "JP2") (pin "4") (pinfunction "4_4") (pintype "passive"))
    )
    (net (code "84") (name "SWDIO") (class "Default")
      (node (ref "IC1") (pin "34") (pinfunction "PA13_34") (pintype "bidirectional"))
      (node (ref "JP2") (pin "3") (pinfunction "3_3") (pintype "passive"))
    )
    (net (code "85") (name "TC_LED") (class "Default")
      (node (ref "IC1") (pin "30") (pinfunction "PA9_30") (pintype "bidirectional"))
      (node (ref "U$9") (pin "1") (pinfunction "G_1") (pintype "passive"))
    )
    (net (code "86") (name "TC_VALUE") (class "Default")
      (node (ref "IC1") (pin "17") (pinfunction "PA7_17") (pintype "bidirectional"))
      (node (ref "TC_POT") (pin "COMMON") (pinfunction "COMMON_COMMON") (pintype "bidirectional"))
    )
    (net (code "87") (name "unconnected-(IC1B-PA10-Pad31)") (class "Default")
      (node (ref "IC1") (pin "31") (pinfunction "PA10_31") (pintype "bidirectional"))
    )
    (net (code "88") (name "unconnected-(IC1B-PA15-Pad38)") (class "Default")
      (node (ref "IC1") (pin "38") (pinfunction "PA15_38") (pintype "bidirectional"))
    )
    (net (code "89") (name "unconnected-(IC1D-PB8-Pad45)") (class "Default")
      (node (ref "IC1") (pin "45") (pinfunction "PB8_45") (pintype "bidirectional"))
    )
    (net (code "90") (name "unconnected-(IC1D-PB9-Pad46)") (class "Default")
      (node (ref "IC1") (pin "46") (pinfunction "PB9_46") (pintype "bidirectional"))
    )
    (net (code "91") (name "unconnected-(IC1D-PB12-Pad25)") (class "Default")
      (node (ref "IC1") (pin "25") (pinfunction "PB12_25") (pintype "bidirectional"))
    )
    (net (code "92") (name "unconnected-(IC1D-PB13-Pad26)") (class "Default")
      (node (ref "IC1") (pin "26") (pinfunction "PB13_26") (pintype "bidirectional"))
    )
    (net (code "93") (name "unconnected-(IC1D-PB14-Pad27)") (class "Default")
      (node (ref "IC1") (pin "27") (pinfunction "PB14_27") (pintype "bidirectional"))
    )
    (net (code "94") (name "unconnected-(IC1D-PB15-Pad28)") (class "Default")
      (node (ref "IC1") (pin "28") (pinfunction "PB15_28") (pintype "bidirectional"))
    )
    (net (code "95") (name "unconnected-(IC1E-PB3-Pad39)") (class "Default")
      (node (ref "IC1") (pin "39") (pinfunction "PB3_39") (pintype "bidirectional"))
    )
    (net (code "96") (name "unconnected-(IC1E-PB4-Pad40)") (class "Default")
      (node (ref "IC1") (pin "40") (pinfunction "PB4_40") (pintype "bidirectional"))
    )
    (net (code "97") (name "unconnected-(IC1E-PB5-Pad41)") (class "Default")
      (node (ref "IC1") (pin "41") (pinfunction "PB5_41") (pintype "bidirectional"))
    )
    (net (code "98") (name "unconnected-(IC1E-PB6-Pad42)") (class "Default")
      (node (ref "IC1") (pin "42") (pinfunction "PB6_42") (pintype "bidirectional"))
    )
    (net (code "99") (name "unconnected-(IC1E-PB7-Pad43)") (class "Default")
      (node (ref "IC1") (pin "43") (pinfunction "PB7_43") (pintype "bidirectional"))
    )
    (net (code "100") (name "unconnected-(IC1F-PC13-Pad2)") (class "Default")
      (node (ref "IC1") (pin "2") (pinfunction "PC13_2") (pintype "bidirectional"))
    )
    (net (code "101") (name "unconnected-(IC1F-PC14-Pad3)") (class "Default")
      (node (ref "IC1") (pin "3") (pinfunction "PC14_3") (pintype "bidirectional"))
    )
    (net (code "102") (name "unconnected-(IC1F-PC15-Pad4)") (class "Default")
      (node (ref "IC1") (pin "4") (pinfunction "PC15_4") (pintype "bidirectional"))
    )
    (net (code "103") (name "unconnected-(IC1G-PD0{slash}OSC<=-Pad5)") (class "Default")
      (node (ref "IC1") (pin "5") (pinfunction "PD0/OSC<=_5") (pintype "bidirectional"))
    )
    (net (code "104") (name "unconnected-(IC1G-PD1{slash}OSC=>-Pad6)") (class "Default")
      (node (ref "IC1") (pin "6") (pinfunction "PD1/OSC=>_6") (pintype "bidirectional"))
    )
    (net (code "105") (name "unconnected-(U$5-Pad2)") (class "Default")
      (node (ref "U$5") (pin "2") (pinfunction "2_2") (pintype "passive"))
    )
    (net (code "106") (name "unconnected-(U$6-STBY-Pad8)") (class "Default")
      (node (ref "U$6") (pin "8") (pinfunction "STBY_8") (pintype "bidirectional"))
    )
  )
)
